# Accelerometer.net
KiCad netlist of a schematic drawn in Altium Designer
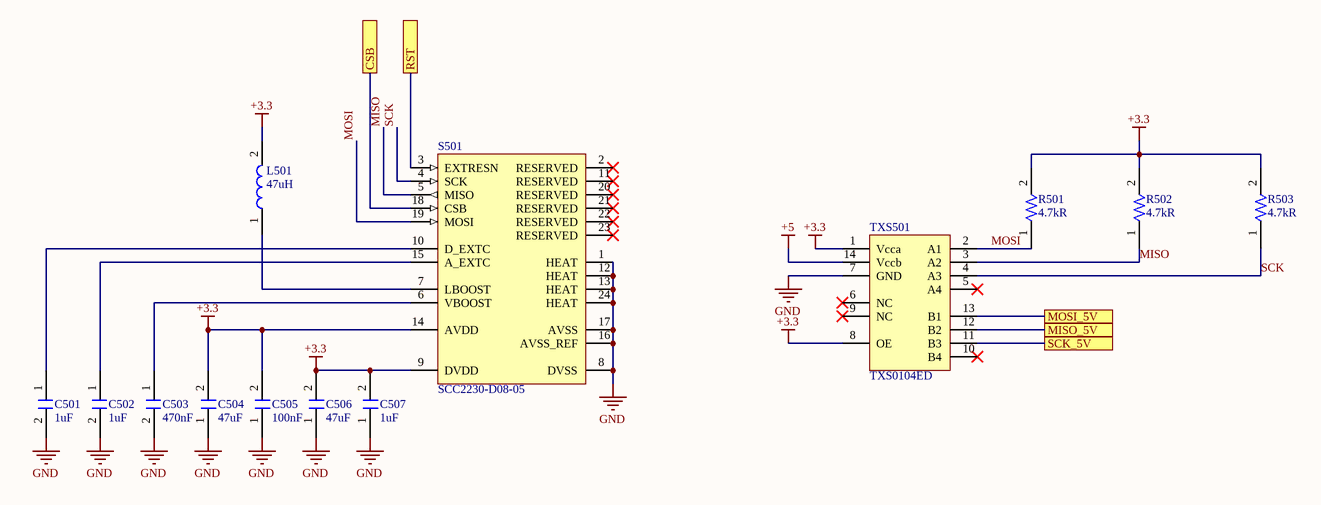
[diagram p0: Accelerometer.SchDoc]

(export (version "E")
  (design (tool "Eeschema 10.0.6"))
  (components
    (comp (ref "C501")
      (value "885012208036")
      (footprint "C1206FNPC-RW")
      (description "Cap Cer 1UF 16V X7R 1206")
      (fields
        (field (name "MANUFACTURER") "Wurth Electronics")
        (field (name "TOLERANCE") "10%")
        (field (name "CAPACITANCE") "1uF")
      )
      (libsource (lib "Passives") (part "C1u-16V-1206FNPC-X7R"))
    )
    (comp (ref "C502")
      (value "885012208036")
      (footprint "C1206FNPC-RW")
      (description "Cap Cer 1UF 16V X7R 1206")
      (fields
        (field (name "MANUFACTURER") "Wurth Electronics")
        (field (name "TOLERANCE") "10%")
        (field (name "CAPACITANCE") "1uF")
      )
      (libsource (lib "Passives") (part "C1u-16V-1206FNPC-X7R"))
    )
    (comp (ref "C503")
      (value "885012208011")
      (footprint "C1206FNPC-RW")
      (description "Cap, 0.47ΜF, 10V, 10%, X7R, 1206")
      (fields (field (name "TOLERANCE") "10%") (field (name "CAPACITANCE") "470nF"))
      (libsource (lib "Passives") (part "C470n-10V-1206FNPC-X7R"))
    )
    (comp (ref "C504")
      (value "885012108012")
      (footprint "C1206FNPC-RW")
      (description "Multilayer Ceramic Capacitor, Wcap-Csgp Series, 47 F, 20%, X5r, 10 V, 1206 [3216 Metric]")
      (fields (field (name "TOLERANCE") "20%") (field (name "CAPACITANCE") "47uF"))
      (libsource (lib "Passives") (part "C47u-10V-1206FNPC-X5R"))
    )
    (comp (ref "C505")
      (value "885012208009")
      (footprint "C1206FNPC-RW")
      (description "Cap, 0.1ΜF, 10V, 10%, X7R, 1206")
      (fields (field (name "TOLERANCE") "10%") (field (name "CAPACITANCE") "100nF"))
      (libsource (lib "Passives") (part "C100n-10V-1206FNPC-X7R"))
    )
    (comp (ref "C506")
      (value "885012108012")
      (footprint "C1206FNPC-RW")
      (description "Multilayer Ceramic Capacitor, Wcap-Csgp Series, 47 F, 20%, X5r, 10 V, 1206 [3216 Metric]")
      (fields (field (name "TOLERANCE") "20%") (field (name "CAPACITANCE") "47uF"))
      (libsource (lib "Passives") (part "C47u-10V-1206FNPC-X5R"))
    )
    (comp (ref "C507")
      (value "885012208036")
      (footprint "C1206FNPC-RW")
      (description "Cap Cer 1UF 16V X7R 1206")
      (fields
        (field (name "MANUFACTURER") "Wurth Electronics")
        (field (name "TOLERANCE") "10%")
        (field (name "CAPACITANCE") "1uF")
      )
      (libsource (lib "Passives") (part "C1u-16V-1206FNPC-X7R"))
    )
    (comp (ref "L501")
      (value "744764147")
      (footprint "L47u-60mA_CF")
      (description "WE-GF Series; Wire-wound SMD Inductor with Ferrite Core; 47 µH")
      (fields (field (name "TOLERANCE") "10%") (field (name "INDUCTANCE") "47uH"))
      (libsource (lib "Passives") (part "L47u-60mA_CF"))
    )
    (comp (ref "R501")
      (value "CRS1206-FX-4701ELF")
      (footprint "R1206FTK-W")
      (description "Res Thick Film 1206 4.7K Ohm 1% 1/2W ±100ppm/°C Molded SMD T/R")
      (fields (field (name "TOLERANCE") "1%") (field (name "RESISTANCE") "4.7kR"))
      (libsource (lib "Passives") (part "R4.7K-1206FTK"))
    )
    (comp (ref "R502")
      (value "CRS1206-FX-4701ELF")
      (footprint "R1206FTK-W")
      (description "Res Thick Film 1206 4.7K Ohm 1% 1/2W ±100ppm/°C Molded SMD T/R")
      (fields (field (name "TOLERANCE") "1%") (field (name "RESISTANCE") "4.7kR"))
      (libsource (lib "Passives") (part "R4.7K-1206FTK"))
    )
    (comp (ref "R503")
      (value "CRS1206-FX-4701ELF")
      (footprint "R1206FTK-W")
      (description "Res Thick Film 1206 4.7K Ohm 1% 1/2W ±100ppm/°C Molded SMD T/R")
      (fields (field (name "TOLERANCE") "1%") (field (name "RESISTANCE") "4.7kR"))
      (libsource (lib "Passives") (part "R4.7K-1206FTK"))
    )
    (comp (ref "S501")
      (value "SCC2230-D08")
      (footprint "Accel_SCC2230-D08")
      (description "Accelerometer and Gyroscope Digital Output 3.3V 24-Pin SOIC T/R")
      (fields (field (name "MANUFACTURER PART NUMBER 1") "SCC2230-D08-05"))
      (libsource (lib "Sensors") (part "Accel_SCC2230-D08"))
    )
    (comp (ref "TXS501")
      (value "TXS0104E")
      (footprint "4bitBVL_TXS0104E")
      (fields (field (name "MANUFACTURER PART NUMBER 1") "TXS0104ED"))
      (libsource (lib "Integrated circuits") (part "4bitBVL_TXS0104E"))
    )
  )
  (nets
    (net (code "1") (name "+3.3") (class "Default")
      (node (ref "C504") (pin "2") (pinfunction "2_2") (pintype "passive"))
      (node (ref "C505") (pin "2") (pinfunction "2_2") (pintype "passive"))
      (node (ref "C506") (pin "2") (pinfunction "2_2") (pintype "passive"))
      (node (ref "C507") (pin "2") (pinfunction "2_2") (pintype "passive"))
      (node (ref "L501") (pin "2") (pinfunction "2_2") (pintype "passive"))
      (node (ref "R501") (pin "2") (pinfunction "2_2") (pintype "passive"))
      (node (ref "R502") (pin "2") (pinfunction "2_2") (pintype "passive"))
      (node (ref "R503") (pin "2") (pinfunction "2_2") (pintype "passive"))
      (node (ref "S501") (pin "14") (pinfunction "AVDD_14") (pintype "passive"))
      (node (ref "S501") (pin "9") (pinfunction "DVDD_9") (pintype "passive"))
      (node (ref "TXS501") (pin "1") (pinfunction "Vcca_1") (pintype "passive"))
      (node (ref "TXS501") (pin "8") (pinfunction "OE_8") (pintype "passive"))
    )
    (net (code "2") (name "+5") (class "Default")
      (node (ref "TXS501") (pin "14") (pinfunction "Vccb_14") (pintype "passive"))
    )
    (net (code "3") (name "/CSB") (class "Default")
      (node (ref "S501") (pin "18") (pinfunction "CSB_18") (pintype "input"))
    )
    (net (code "4") (name "/MISO") (class "Default")
      (node (ref "R502") (pin "1") (pinfunction "1_1") (pintype "passive"))
      (node (ref "S501") (pin "5") (pinfunction "MISO_5") (pintype "output"))
      (node (ref "TXS501") (pin "3") (pinfunction "A2_3") (pintype "passive"))
    )
    (net (code "5") (name "/MISO_5V") (class "Default")
      (node (ref "TXS501") (pin "12") (pinfunction "B2_12") (pintype "passive"))
    )
    (net (code "6") (name "/MOSI") (class "Default")
      (node (ref "R501") (pin "1") (pinfunction "1_1") (pintype "passive"))
      (node (ref "S501") (pin "19") (pinfunction "MOSI_19") (pintype "input"))
      (node (ref "TXS501") (pin "2") (pinfunction "A1_2") (pintype "passive"))
    )
    (net (code "7") (name "/MOSI_5V") (class "Default")
      (node (ref "TXS501") (pin "13") (pinfunction "B1_13") (pintype "passive"))
    )
    (net (code "8") (name "/RST") (class "Default")
      (node (ref "S501") (pin "3") (pinfunction "EXTRESN_3") (pintype "input"))
    )
    (net (code "9") (name "/SCK") (class "Default")
      (node (ref "R503") (pin "1") (pinfunction "1_1") (pintype "passive"))
      (node (ref "S501") (pin "4") (pinfunction "SCK_4") (pintype "input"))
      (node (ref "TXS501") (pin "4") (pinfunction "A3_4") (pintype "passive"))
    )
    (net (code "10") (name "/SCK_5V") (class "Default")
      (node (ref "TXS501") (pin "11") (pinfunction "B3_11") (pintype "passive"))
    )
    (net (code "11") (name "GND") (class "Default")
      (node (ref "C501") (pin "2") (pinfunction "2_2") (pintype "passive"))
      (node (ref "C502") (pin "2") (pinfunction "2_2") (pintype "passive"))
      (node (ref "C503") (pin "2") (pinfunction "2_2") (pintype "passive"))
      (node (ref "C504") (pin "1") (pinfunction "1_1") (pintype "passive"))
      (node (ref "C505") (pin "1") (pinfunction "1_1") (pintype "passive"))
      (node (ref "C506") (pin "1") (pinfunction "1_1") (pintype "passive"))
      (node (ref "C507") (pin "1") (pinfunction "1_1") (pintype "passive"))
      (node (ref "S501") (pin "1") (pinfunction "HEAT_1") (pintype "passive"))
      (node (ref "S501") (pin "12") (pinfunction "HEAT_12") (pintype "passive"))
      (node (ref "S501") (pin "13") (pinfunction "HEAT_13") (pintype "passive"))
      (node (ref "S501") (pin "16") (pinfunction "AVSS_REF_16") (pintype "passive"))
      (node (ref "S501") (pin "17") (pinfunction "AVSS_17") (pintype "passive"))
      (node (ref "S501") (pin "24") (pinfunction "HEAT_24") (pintype "passive"))
      (node (ref "S501") (pin "8") (pinfunction "DVSS_8") (pintype "passive"))
      (node (ref "TXS501") (pin "7") (pinfunction "GND_7") (pintype "passive"))
    )
    (net (code "12") (name "Net-(S501-A_EXTC)") (class "Default")
      (node (ref "C502") (pin "1") (pinfunction "1_1") (pintype "passive"))
      (node (ref "S501") (pin "15") (pinfunction "A_EXTC_15") (pintype "passive"))
    )
    (net (code "13") (name "Net-(S501-D_EXTC)") (class "Default")
      (node (ref "C501") (pin "1") (pinfunction "1_1") (pintype "passive"))
      (node (ref "S501") (pin "10") (pinfunction "D_EXTC_10") (pintype "passive"))
    )
    (net (code "14") (name "Net-(S501-LBOOST)") (class "Default")
      (node (ref "L501") (pin "1") (pinfunction "1_1") (pintype "passive"))
      (node (ref "S501") (pin "7") (pinfunction "LBOOST_7") (pintype "passive"))
    )
    (net (code "15") (name "Net-(S501-VBOOST)") (class "Default")
      (node (ref "C503") (pin "1") (pinfunction "1_1") (pintype "passive"))
      (node (ref "S501") (pin "6") (pinfunction "VBOOST_6") (pintype "passive"))
    )
    (net (code "16") (name "unconnected-(S501-RESERVED-Pad2)") (class "Default")
      (node (ref "S501") (pin "2") (pinfunction "RESERVED_2") (pintype "passive+no_connect"))
    )
    (net (code "17") (name "unconnected-(S501-RESERVED-Pad11)") (class "Default")
      (node (ref "S501") (pin "11") (pinfunction "RESERVED_11") (pintype "passive+no_connect"))
    )
    (net (code "18") (name "unconnected-(S501-RESERVED-Pad20)") (class "Default")
      (node (ref "S501") (pin "20") (pinfunction "RESERVED_20") (pintype "passive+no_connect"))
    )
    (net (code "19") (name "unconnected-(S501-RESERVED-Pad21)") (class "Default")
      (node (ref "S501") (pin "21") (pinfunction "RESERVED_21") (pintype "passive+no_connect"))
    )
    (net (code "20") (name "unconnected-(S501-RESERVED-Pad22)") (class "Default")
      (node (ref "S501") (pin "22") (pinfunction "RESERVED_22") (pintype "passive+no_connect"))
    )
    (net (code "21") (name "unconnected-(S501-RESERVED-Pad23)") (class "Default")
      (node (ref "S501") (pin "23") (pinfunction "RESERVED_23") (pintype "passive+no_connect"))
    )
    (net (code "22") (name "unconnected-(TXS501-A4-Pad5)") (class "Default")
      (node (ref "TXS501") (pin "5") (pinfunction "A4_5") (pintype "passive+no_connect"))
    )
    (net (code "23") (name "unconnected-(TXS501-B4-Pad10)") (class "Default")
      (node (ref "TXS501") (pin "10") (pinfunction "B4_10") (pintype "passive+no_connect"))
    )
    (net (code "24") (name "unconnected-(TXS501-NC-Pad6)") (class "Default")
      (node (ref "TXS501") (pin "6") (pinfunction "NC_6") (pintype "passive+no_connect"))
    )
    (net (code "25") (name "unconnected-(TXS501-NC-Pad9)") (class "Default")
      (node (ref "TXS501") (pin "9") (pinfunction "NC_9") (pintype "passive+no_connect"))
    )
  )
)
